# RobotShieldInterfaceRevB.net
KiCad netlist of a schematic drawn in EAGLE
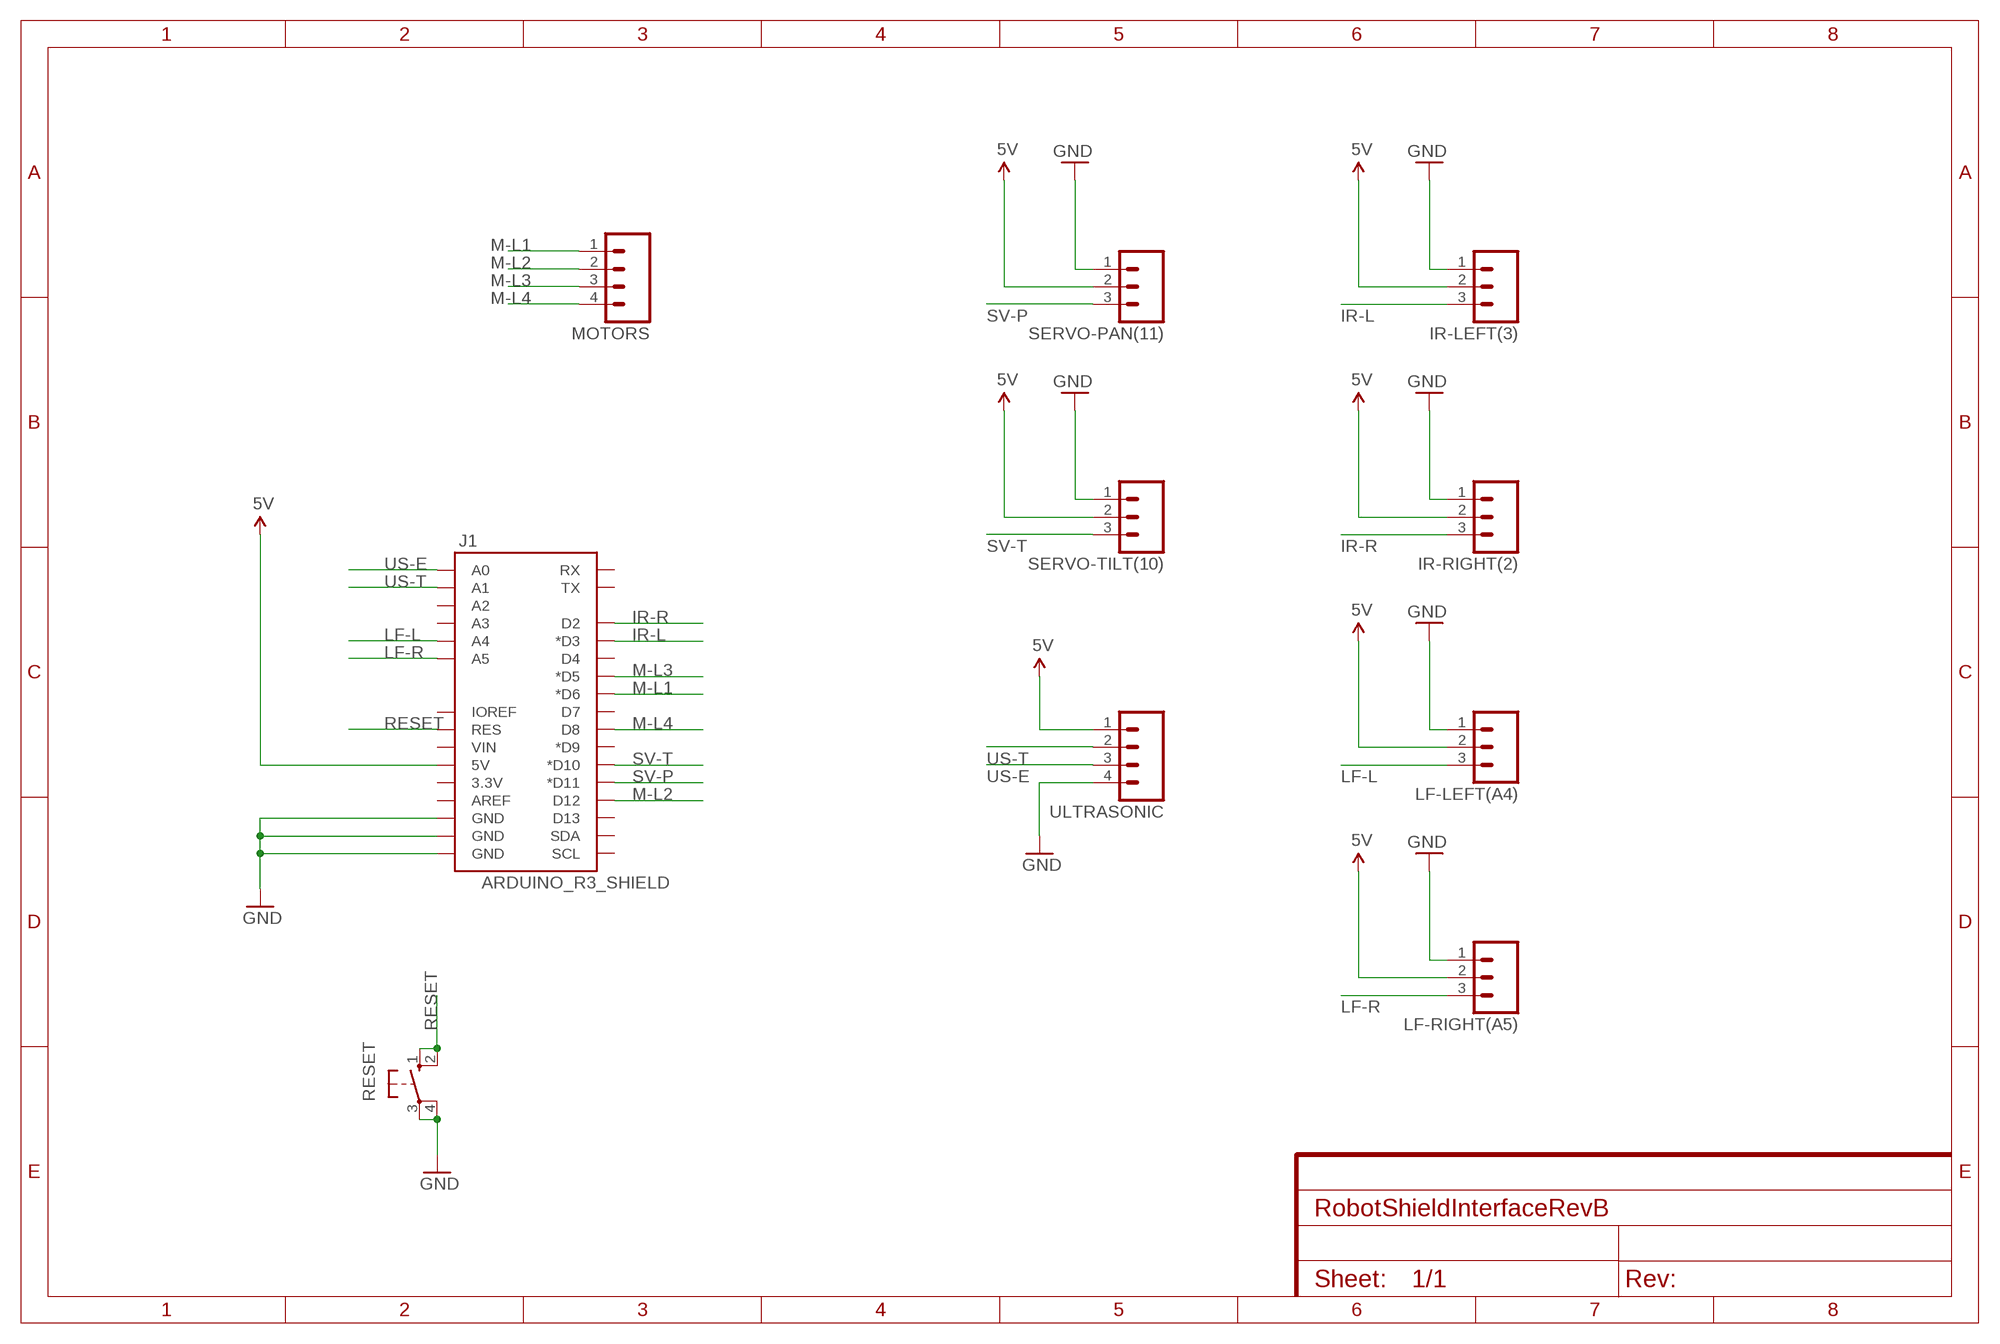
[diagram p0: schematic, sheet 1]

(export (version "E")
  (design (tool "Eeschema 10.0.6"))
  (components
    (comp (ref "IR-LEFT(3)")
      (value "M03PTH")
      (footprint "eagle-import:1X03")
      (libsource (lib "eagle-import") (part "M03PTH"))
    )
    (comp (ref "IR-RIGHT(2)")
      (value "M03PTH")
      (footprint "eagle-import:1X03")
      (libsource (lib "eagle-import") (part "M03PTH"))
    )
    (comp (ref "J1")
      (value "ARDUINO_R3_SHIELD")
      (footprint "eagle-import:UNO_R3_SHIELD")
      (libsource (lib "eagle-import") (part "ARDUINO_R3_SHIELD"))
    )
    (comp (ref "LF-LEFT(A4)")
      (value "M03PTH")
      (footprint "eagle-import:1X03")
      (libsource (lib "eagle-import") (part "M03PTH"))
    )
    (comp (ref "LF-RIGHT(A5)")
      (value "M03PTH")
      (footprint "eagle-import:1X03")
      (libsource (lib "eagle-import") (part "M03PTH"))
    )
    (comp (ref "MOTORS")
      (value "M04PTH")
      (footprint "eagle-import:1X04")
      (libsource (lib "eagle-import") (part "M04PTH"))
    )
    (comp (ref "RESET")
      (value "10-XX")
      (footprint "eagle-import:B3F-10XX")
      (fields (field (name "MPN") "B3F-1000"))
      (libsource (lib "eagle-import") (part "10-XX"))
    )
    (comp (ref "SERVO-PAN(11)")
      (value "M03PTH")
      (footprint "eagle-import:1X03")
      (libsource (lib "eagle-import") (part "M03PTH"))
    )
    (comp (ref "SERVO-TILT(10)")
      (value "M03PTH")
      (footprint "eagle-import:1X03")
      (libsource (lib "eagle-import") (part "M03PTH"))
    )
    (comp (ref "ULTRASONIC")
      (value "M04PTH")
      (footprint "eagle-import:1X04")
      (libsource (lib "eagle-import") (part "M04PTH"))
    )
  )
  (nets
    (net (code "1") (name "/IR-L") (class "Default")
      (node (ref "IR-LEFT(3)") (pin "3") (pinfunction "3_3") (pintype "passive"))
      (node (ref "J1") (pin "D3") (pinfunction "*D3_D3") (pintype "bidirectional"))
    )
    (net (code "2") (name "/IR-R") (class "Default")
      (node (ref "IR-RIGHT(2)") (pin "3") (pinfunction "3_3") (pintype "passive"))
      (node (ref "J1") (pin "D2") (pinfunction "D2_D2") (pintype "bidirectional"))
    )
    (net (code "3") (name "/LF-L") (class "Default")
      (node (ref "J1") (pin "A4") (pinfunction "A4_A4") (pintype "bidirectional"))
      (node (ref "LF-LEFT(A4)") (pin "3") (pinfunction "3_3") (pintype "passive"))
    )
    (net (code "4") (name "/LF-R") (class "Default")
      (node (ref "J1") (pin "A5") (pinfunction "A5_A5") (pintype "bidirectional"))
      (node (ref "LF-RIGHT(A5)") (pin "3") (pinfunction "3_3") (pintype "passive"))
    )
    (net (code "5") (name "/M-L1") (class "Default")
      (node (ref "J1") (pin "D6") (pinfunction "*D6_D6") (pintype "bidirectional"))
      (node (ref "MOTORS") (pin "1") (pinfunction "1_1") (pintype "passive"))
    )
    (net (code "6") (name "/M-L2") (class "Default")
      (node (ref "J1") (pin "D12") (pinfunction "D12_D12") (pintype "bidirectional"))
      (node (ref "MOTORS") (pin "2") (pinfunction "2_2") (pintype "passive"))
    )
    (net (code "7") (name "/M-L3") (class "Default")
      (node (ref "J1") (pin "D5") (pinfunction "*D5_D5") (pintype "bidirectional"))
      (node (ref "MOTORS") (pin "3") (pinfunction "3_3") (pintype "passive"))
    )
    (net (code "8") (name "/M-L4") (class "Default")
      (node (ref "J1") (pin "D8") (pinfunction "D8_D8") (pintype "bidirectional"))
      (node (ref "MOTORS") (pin "4") (pinfunction "4_4") (pintype "passive"))
    )
    (net (code "9") (name "/RESET") (class "Default")
      (node (ref "J1") (pin "RES") (pinfunction "RES_RES") (pintype "bidirectional"))
      (node (ref "RESET") (pin "1") (pinfunction "S_1") (pintype "passive"))
      (node (ref "RESET") (pin "2") (pinfunction "S1_2") (pintype "passive"))
    )
    (net (code "10") (name "/SV-P") (class "Default")
      (node (ref "J1") (pin "D11") (pinfunction "*D11_D11") (pintype "bidirectional"))
      (node (ref "SERVO-PAN(11)") (pin "3") (pinfunction "3_3") (pintype "passive"))
    )
    (net (code "11") (name "/SV-T") (class "Default")
      (node (ref "J1") (pin "D10") (pinfunction "*D10_D10") (pintype "bidirectional"))
      (node (ref "SERVO-TILT(10)") (pin "3") (pinfunction "3_3") (pintype "passive"))
    )
    (net (code "12") (name "/US-E") (class "Default")
      (node (ref "J1") (pin "A0") (pinfunction "A0_A0") (pintype "bidirectional"))
      (node (ref "ULTRASONIC") (pin "3") (pinfunction "3_3") (pintype "passive"))
    )
    (net (code "13") (name "/US-T") (class "Default")
      (node (ref "J1") (pin "A1") (pinfunction "A1_A1") (pintype "bidirectional"))
      (node (ref "ULTRASONIC") (pin "2") (pinfunction "2_2") (pintype "passive"))
    )
    (net (code "14") (name "5V") (class "Default")
      (node (ref "IR-LEFT(3)") (pin "2") (pinfunction "2_2") (pintype "passive"))
      (node (ref "IR-RIGHT(2)") (pin "2") (pinfunction "2_2") (pintype "passive"))
      (node (ref "J1") (pin "5V") (pinfunction "5V_5V") (pintype "bidirectional"))
      (node (ref "LF-LEFT(A4)") (pin "2") (pinfunction "2_2") (pintype "passive"))
      (node (ref "LF-RIGHT(A5)") (pin "2") (pinfunction "2_2") (pintype "passive"))
      (node (ref "SERVO-PAN(11)") (pin "2") (pinfunction "2_2") (pintype "passive"))
      (node (ref "SERVO-TILT(10)") (pin "2") (pinfunction "2_2") (pintype "passive"))
      (node (ref "ULTRASONIC") (pin "1") (pinfunction "1_1") (pintype "passive"))
    )
    (net (code "15") (name "GND") (class "Default")
      (node (ref "IR-LEFT(3)") (pin "1") (pinfunction "1_1") (pintype "passive"))
      (node (ref "IR-RIGHT(2)") (pin "1") (pinfunction "1_1") (pintype "passive"))
      (node (ref "J1") (pin "GND@0") (pinfunction "GND_GND@0") (pintype "bidirectional"))
      (node (ref "J1") (pin "GND@1") (pinfunction "GND_GND@1") (pintype "bidirectional"))
      (node (ref "J1") (pin "GND@2") (pinfunction "GND_GND@2") (pintype "bidirectional"))
      (node (ref "LF-LEFT(A4)") (pin "1") (pinfunction "1_1") (pintype "passive"))
      (node (ref "LF-RIGHT(A5)") (pin "1") (pinfunction "1_1") (pintype "passive"))
      (node (ref "RESET") (pin "3") (pinfunction "P_3") (pintype "passive"))
      (node (ref "RESET") (pin "4") (pinfunction "P1_4") (pintype "passive"))
      (node (ref "SERVO-PAN(11)") (pin "1") (pinfunction "1_1") (pintype "passive"))
      (node (ref "SERVO-TILT(10)") (pin "1") (pinfunction "1_1") (pintype "passive"))
      (node (ref "ULTRASONIC") (pin "4") (pinfunction "4_4") (pintype "passive"))
    )
    (net (code "16") (name "unconnected-(J1-*D9-PadD9)") (class "Default")
      (node (ref "J1") (pin "D9") (pinfunction "*D9_D9") (pintype "bidirectional"))
    )
    (net (code "17") (name "unconnected-(J1-Pad3.3V)") (class "Default")
      (node (ref "J1") (pin "3.3V") (pinfunction "3.3V_3.3V") (pintype "bidirectional"))
    )
    (net (code "18") (name "unconnected-(J1-PadA2)") (class "Default")
      (node (ref "J1") (pin "A2") (pinfunction "A2_A2") (pintype "bidirectional"))
    )
    (net (code "19") (name "unconnected-(J1-PadA3)") (class "Default")
      (node (ref "J1") (pin "A3") (pinfunction "A3_A3") (pintype "bidirectional"))
    )
    (net (code "20") (name "unconnected-(J1-PadAREF)") (class "Default")
      (node (ref "J1") (pin "AREF") (pinfunction "AREF_AREF") (pintype "bidirectional"))
    )
    (net (code "21") (name "unconnected-(J1-PadD4)") (class "Default")
      (node (ref "J1") (pin "D4") (pinfunction "D4_D4") (pintype "bidirectional"))
    )
    (net (code "22") (name "unconnected-(J1-PadD7)") (class "Default")
      (node (ref "J1") (pin "D7") (pinfunction "D7_D7") (pintype "bidirectional"))
    )
    (net (code "23") (name "unconnected-(J1-PadD13)") (class "Default")
      (node (ref "J1") (pin "D13") (pinfunction "D13_D13") (pintype "bidirectional"))
    )
    (net (code "24") (name "unconnected-(J1-PadIOREF)") (class "Default")
      (node (ref "J1") (pin "IOREF") (pinfunction "IOREF_IOREF") (pintype "bidirectional"))
    )
    (net (code "25") (name "unconnected-(J1-PadRX)") (class "Default")
      (node (ref "J1") (pin "RX") (pinfunction "RX_RX") (pintype "bidirectional"))
    )
    (net (code "26") (name "unconnected-(J1-PadSCL)") (class "Default")
      (node (ref "J1") (pin "SCL") (pinfunction "SCL_SCL") (pintype "bidirectional"))
    )
    (net (code "27") (name "unconnected-(J1-PadSDA)") (class "Default")
      (node (ref "J1") (pin "SDA") (pinfunction "SDA_SDA") (pintype "bidirectional"))
    )
    (net (code "28") (name "unconnected-(J1-PadTX)") (class "Default")
      (node (ref "J1") (pin "TX") (pinfunction "TX_TX") (pintype "bidirectional"))
    )
    (net (code "29") (name "unconnected-(J1-PadVIN)") (class "Default")
      (node (ref "J1") (pin "VIN") (pinfunction "VIN_VIN") (pintype "bidirectional"))
    )
  )
)
